# Heads_Up_LEDs.net
KiCad netlist of a schematic drawn in EAGLE
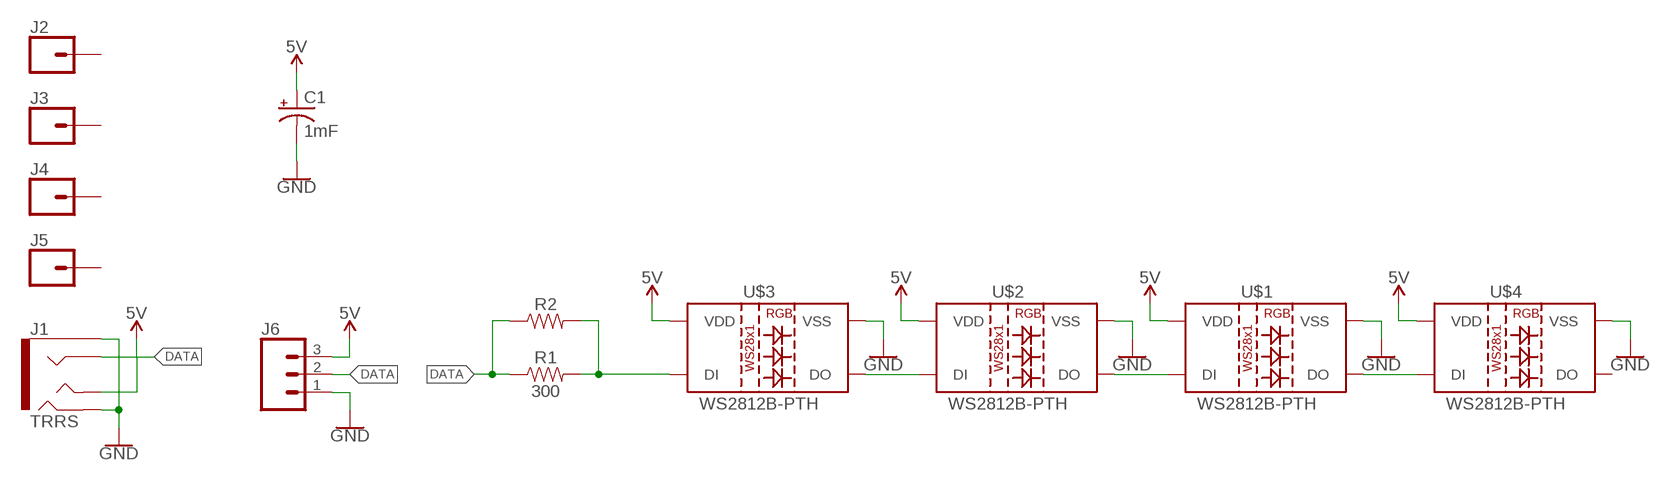
[diagram p0: schematic, sheet 1]

(export (version "E")
  (design (tool "Eeschema 10.0.6"))
  (components
    (comp (ref "C1")
      (value "1mF")
      (footprint "eagle-import:CPOL-RADIAL-5MM-10MM")
      (libsource (lib "eagle-import") (part "1000UF-RADIAL-5MM-25V-20%"))
    )
    (comp (ref "J1")
      (value "TRRS")
      (footprint "eagle-import:AUDIO_JACK_3.5MM_TRRS_SMD_RA")
      (libsource (lib "eagle-import") (part "AUDIO_JACK_TRRSSMD_RA"))
    )
    (comp (ref "J2")
      (value "CONN_01OFFSET")
      (footprint "eagle-import:1X01_OFFSET")
      (libsource (lib "eagle-import") (part "CONN_01OFFSET"))
    )
    (comp (ref "J3")
      (value "CONN_01OFFSET")
      (footprint "eagle-import:1X01_OFFSET")
      (libsource (lib "eagle-import") (part "CONN_01OFFSET"))
    )
    (comp (ref "J4")
      (value "CONN_01OFFSET")
      (footprint "eagle-import:1X01_OFFSET")
      (libsource (lib "eagle-import") (part "CONN_01OFFSET"))
    )
    (comp (ref "J5")
      (value "CONN_01OFFSET")
      (footprint "eagle-import:1X01_OFFSET")
      (libsource (lib "eagle-import") (part "CONN_01OFFSET"))
    )
    (comp (ref "J6")
      (value "CONN_03")
      (footprint "eagle-import:1X03")
      (libsource (lib "eagle-import") (part "CONN_03"))
    )
    (comp (ref "R1")
      (value "300")
      (footprint "eagle-import:0603")
      (libsource (lib "eagle-import") (part "300OHM-0603-1/10W-1%"))
    )
    (comp (ref "R2")
      (value "RESISTORAXIAL-0.3")
      (footprint "eagle-import:AXIAL-0.3")
      (libsource (lib "eagle-import") (part "RESISTORAXIAL-0.3"))
    )
    (comp (ref "U$1")
      (value "WS2812B-PTH")
      (footprint "eagle-import:WS2812B-PTH-KIT")
      (libsource (lib "eagle-import") (part "WS2812B-PTH"))
    )
    (comp (ref "U$2")
      (value "WS2812B-PTH")
      (footprint "eagle-import:WS2812B-PTH-KIT")
      (libsource (lib "eagle-import") (part "WS2812B-PTH"))
    )
    (comp (ref "U$3")
      (value "WS2812B-PTH")
      (footprint "eagle-import:WS2812B-PTH-KIT")
      (libsource (lib "eagle-import") (part "WS2812B-PTH"))
    )
    (comp (ref "U$4")
      (value "WS2812B-PTH")
      (footprint "eagle-import:WS2812B-PTH-KIT")
      (libsource (lib "eagle-import") (part "WS2812B-PTH"))
    )
  )
  (nets
    (net (code "1") (name "5V") (class "Default")
      (node (ref "C1") (pin "+") (pinfunction "+_+") (pintype "passive"))
      (node (ref "J1") (pin "TIP") (pinfunction "TIP_TIP") (pintype "bidirectional"))
      (node (ref "J6") (pin "3") (pinfunction "3_3") (pintype "passive"))
      (node (ref "U$1") (pin "2") (pinfunction "VDD_2") (pintype "bidirectional"))
      (node (ref "U$2") (pin "2") (pinfunction "VDD_2") (pintype "bidirectional"))
      (node (ref "U$3") (pin "2") (pinfunction "VDD_2") (pintype "bidirectional"))
      (node (ref "U$4") (pin "2") (pinfunction "VDD_2") (pintype "bidirectional"))
    )
    (net (code "2") (name "DATA") (class "Default")
      (node (ref "J1") (pin "RING1") (pinfunction "RING1_RING1") (pintype "bidirectional"))
      (node (ref "J6") (pin "2") (pinfunction "2_2") (pintype "passive"))
      (node (ref "R1") (pin "1") (pinfunction "1_1") (pintype "passive"))
      (node (ref "R2") (pin "P$1") (pinfunction "1_P$1") (pintype "passive"))
    )
    (net (code "3") (name "GND") (class "Default")
      (node (ref "C1") (pin "-") (pinfunction "-_-") (pintype "passive"))
      (node (ref "J1") (pin "EARTH") (pinfunction "EARTH_EARTH") (pintype "bidirectional"))
      (node (ref "J1") (pin "RING2") (pinfunction "RING2_RING2") (pintype "bidirectional"))
      (node (ref "J6") (pin "1") (pinfunction "1_1") (pintype "passive"))
      (node (ref "U$1") (pin "3") (pinfunction "VSS_3") (pintype "bidirectional"))
      (node (ref "U$2") (pin "3") (pinfunction "VSS_3") (pintype "bidirectional"))
      (node (ref "U$3") (pin "3") (pinfunction "VSS_3") (pintype "bidirectional"))
      (node (ref "U$4") (pin "3") (pinfunction "VSS_3") (pintype "bidirectional"))
    )
    (net (code "4") (name "Net-(R2-2)") (class "Default")
      (node (ref "R1") (pin "2") (pinfunction "2_2") (pintype "passive"))
      (node (ref "R2") (pin "P$2") (pinfunction "2_P$2") (pintype "passive"))
      (node (ref "U$3") (pin "1") (pinfunction "DI_1") (pintype "bidirectional"))
    )
    (net (code "5") (name "Net-(U$1-DI)") (class "Default")
      (node (ref "U$1") (pin "1") (pinfunction "DI_1") (pintype "bidirectional"))
      (node (ref "U$2") (pin "4") (pinfunction "DO_4") (pintype "bidirectional"))
    )
    (net (code "6") (name "Net-(U$1-DO)") (class "Default")
      (node (ref "U$1") (pin "4") (pinfunction "DO_4") (pintype "bidirectional"))
      (node (ref "U$4") (pin "1") (pinfunction "DI_1") (pintype "bidirectional"))
    )
    (net (code "7") (name "Net-(U$2-DI)") (class "Default")
      (node (ref "U$2") (pin "1") (pinfunction "DI_1") (pintype "bidirectional"))
      (node (ref "U$3") (pin "4") (pinfunction "DO_4") (pintype "bidirectional"))
    )
    (net (code "8") (name "unconnected-(J2-Pad1)") (class "Default")
      (node (ref "J2") (pin "1") (pinfunction "1_1") (pintype "passive"))
    )
    (net (code "9") (name "unconnected-(J3-Pad1)") (class "Default")
      (node (ref "J3") (pin "1") (pinfunction "1_1") (pintype "passive"))
    )
    (net (code "10") (name "unconnected-(J4-Pad1)") (class "Default")
      (node (ref "J4") (pin "1") (pinfunction "1_1") (pintype "passive"))
    )
    (net (code "11") (name "unconnected-(J5-Pad1)") (class "Default")
      (node (ref "J5") (pin "1") (pinfunction "1_1") (pintype "passive"))
    )
    (net (code "12") (name "unconnected-(U$4-DO-Pad4)") (class "Default")
      (node (ref "U$4") (pin "4") (pinfunction "DO_4") (pintype "bidirectional"))
    )
  )
)
